# Battle_Switch.net
KiCad netlist of a schematic drawn in EAGLE
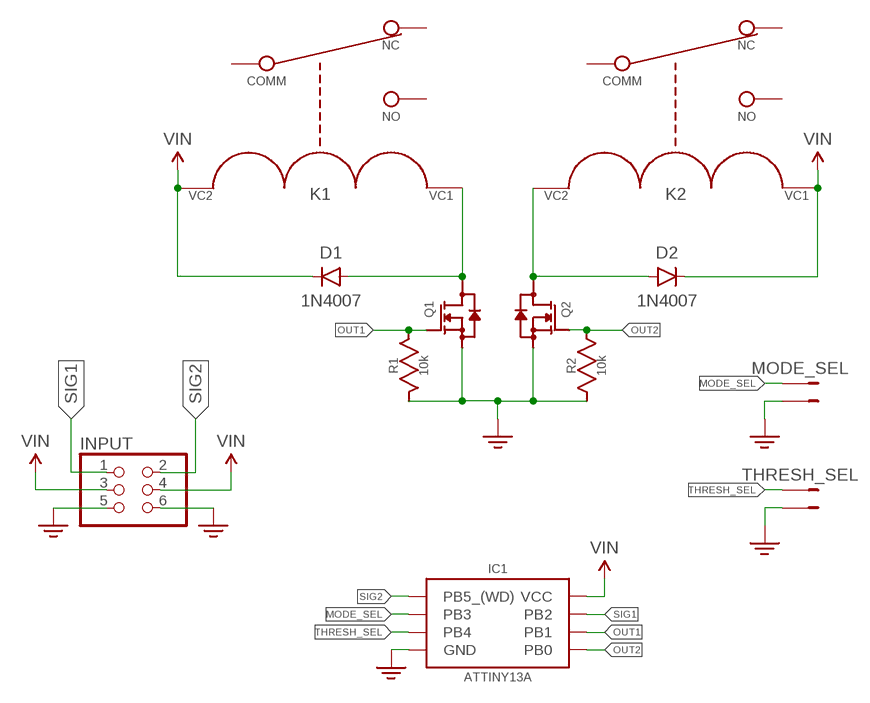
[diagram p0: schematic, sheet 1]

(export (version "E")
  (design (tool "Eeschema 10.0.6"))
  (components
    (comp (ref "D1")
      (value "1N4007")
      (footprint "eagle-import:DIODE-1N4001")
      (libsource (lib "eagle-import") (part "DIODEPTH"))
    )
    (comp (ref "D2")
      (value "1N4007")
      (footprint "eagle-import:DIODE-1N4001")
      (libsource (lib "eagle-import") (part "DIODEPTH"))
    )
    (comp (ref "IC1")
      (value "ATTINY13A")
      (footprint "eagle-import:8-PDIP")
      (libsource (lib "eagle-import") (part "ATTINY13A"))
    )
    (comp (ref "INPUT")
      (value "PINHD-2X3")
      (footprint "eagle-import:2X03")
      (libsource (lib "eagle-import") (part "PINHD-2X3"))
    )
    (comp (ref "K1")
      (value "AZ2100-1C-5DE")
      (footprint "eagle-import:AZ2100")
      (libsource (lib "eagle-import") (part "AZ2100-1C-5DE"))
    )
    (comp (ref "K2")
      (value "AZ2100-1C-5DE")
      (footprint "eagle-import:AZ2100")
      (libsource (lib "eagle-import") (part "AZ2100-1C-5DE"))
    )
    (comp (ref "MODE_SEL")
      (value "JUMPER-PTH-2-NO")
      (footprint "eagle-import:PTH-JUMPER-2-NO")
      (libsource (lib "eagle-import") (part "JUMPER-PTH-2-NO"))
    )
    (comp (ref "Q1")
      (value "BS170")
      (footprint "eagle-import:TO-92-AMMO")
      (libsource (lib "eagle-import") (part "BS170"))
    )
    (comp (ref "Q2")
      (value "BS170")
      (footprint "eagle-import:TO-92-AMMO")
      (libsource (lib "eagle-import") (part "BS170"))
    )
    (comp (ref "R1")
      (value "10k")
      (footprint "eagle-import:0411_15")
      (libsource (lib "eagle-import") (part "RESISTOR"))
    )
    (comp (ref "R2")
      (value "10k")
      (footprint "eagle-import:0411_15")
      (libsource (lib "eagle-import") (part "RESISTOR"))
    )
    (comp (ref "THRESH_SEL")
      (value "JUMPER-PTH-2-NO")
      (footprint "eagle-import:PTH-JUMPER-2-NO")
      (libsource (lib "eagle-import") (part "JUMPER-PTH-2-NO"))
    )
  )
  (nets
    (net (code "1") (name "GND") (class "Default")
      (node (ref "IC1") (pin "P$4") (pinfunction "GND_P$4") (pintype "power_in"))
      (node (ref "INPUT") (pin "5") (pinfunction "5_5") (pintype "passive"))
      (node (ref "INPUT") (pin "6") (pinfunction "6_6") (pintype "passive"))
      (node (ref "MODE_SEL") (pin "P$2") (pinfunction "2_P$2") (pintype "passive"))
      (node (ref "Q1") (pin "1") (pinfunction "SOURCE_1") (pintype "passive"))
      (node (ref "Q2") (pin "1") (pinfunction "SOURCE_1") (pintype "passive"))
      (node (ref "R1") (pin "2") (pinfunction "P$2_2") (pintype "passive"))
      (node (ref "R2") (pin "1") (pinfunction "P$1_1") (pintype "passive"))
      (node (ref "THRESH_SEL") (pin "P$2") (pinfunction "2_P$2") (pintype "passive"))
    )
    (net (code "2") (name "MODE_SEL") (class "Default")
      (node (ref "IC1") (pin "P$2") (pinfunction "PB3_P$2") (pintype "bidirectional"))
      (node (ref "MODE_SEL") (pin "P$1") (pinfunction "1_P$1") (pintype "passive"))
    )
    (net (code "3") (name "Net-(Q1-DRAIN)") (class "Default")
      (node (ref "D1") (pin "A") (pinfunction "A_A") (pintype "passive"))
      (node (ref "K1") (pin "VC1") (pinfunction "VC1_VC1") (pintype "passive"))
      (node (ref "Q1") (pin "3") (pinfunction "DRAIN_3") (pintype "passive"))
    )
    (net (code "4") (name "Net-(Q2-DRAIN)") (class "Default")
      (node (ref "D2") (pin "A") (pinfunction "A_A") (pintype "passive"))
      (node (ref "K2") (pin "VC2") (pinfunction "VC2_VC2") (pintype "passive"))
      (node (ref "Q2") (pin "3") (pinfunction "DRAIN_3") (pintype "passive"))
    )
    (net (code "5") (name "OUT1") (class "Default")
      (node (ref "IC1") (pin "P$6") (pinfunction "PB1_P$6") (pintype "bidirectional"))
      (node (ref "Q1") (pin "2") (pinfunction "GATE_2") (pintype "passive"))
      (node (ref "R1") (pin "1") (pinfunction "P$1_1") (pintype "passive"))
    )
    (net (code "6") (name "OUT2") (class "Default")
      (node (ref "IC1") (pin "P$5") (pinfunction "PB0_P$5") (pintype "bidirectional"))
      (node (ref "Q2") (pin "2") (pinfunction "GATE_2") (pintype "passive"))
      (node (ref "R2") (pin "2") (pinfunction "P$2_2") (pintype "passive"))
    )
    (net (code "7") (name "SIG1") (class "Default")
      (node (ref "IC1") (pin "P$7") (pinfunction "PB2_P$7") (pintype "bidirectional"))
      (node (ref "INPUT") (pin "1") (pinfunction "1_1") (pintype "passive"))
    )
    (net (code "8") (name "SIG2") (class "Default")
      (node (ref "IC1") (pin "P$1") (pinfunction "PB5_(WD)_P$1") (pintype "bidirectional"))
      (node (ref "INPUT") (pin "2") (pinfunction "2_2") (pintype "passive"))
    )
    (net (code "9") (name "THRESH_SEL") (class "Default")
      (node (ref "IC1") (pin "P$3") (pinfunction "PB4_P$3") (pintype "bidirectional"))
      (node (ref "THRESH_SEL") (pin "P$1") (pinfunction "1_P$1") (pintype "passive"))
    )
    (net (code "10") (name "VIN") (class "Default")
      (node (ref "D1") (pin "C") (pinfunction "C_C") (pintype "passive"))
      (node (ref "D2") (pin "C") (pinfunction "C_C") (pintype "passive"))
      (node (ref "IC1") (pin "P$8") (pinfunction "VCC_P$8") (pintype "power_in"))
      (node (ref "INPUT") (pin "3") (pinfunction "3_3") (pintype "passive"))
      (node (ref "INPUT") (pin "4") (pinfunction "4_4") (pintype "passive"))
      (node (ref "K1") (pin "VC2") (pinfunction "VC2_VC2") (pintype "passive"))
      (node (ref "K2") (pin "VC1") (pinfunction "VC1_VC1") (pintype "passive"))
    )
    (net (code "11") (name "unconnected-(K1-PadCOMM)") (class "Default")
      (node (ref "K1") (pin "COMM") (pinfunction "COMM_COMM") (pintype "bidirectional"))
    )
    (net (code "12") (name "unconnected-(K1-PadNC)") (class "Default")
      (node (ref "K1") (pin "NC") (pinfunction "NC_NC") (pintype "bidirectional"))
    )
    (net (code "13") (name "unconnected-(K1-PadNO)") (class "Default")
      (node (ref "K1") (pin "NO") (pinfunction "NO_NO") (pintype "bidirectional"))
    )
    (net (code "14") (name "unconnected-(K2-PadCOMM)") (class "Default")
      (node (ref "K2") (pin "COMM") (pinfunction "COMM_COMM") (pintype "bidirectional"))
    )
    (net (code "15") (name "unconnected-(K2-PadNC)") (class "Default")
      (node (ref "K2") (pin "NC") (pinfunction "NC_NC") (pintype "bidirectional"))
    )
    (net (code "16") (name "unconnected-(K2-PadNO)") (class "Default")
      (node (ref "K2") (pin "NO") (pinfunction "NO_NO") (pintype "bidirectional"))
    )
  )
)
